# T03-GSM-Schematic.net
KiCad netlist of a schematic drawn in EAGLE
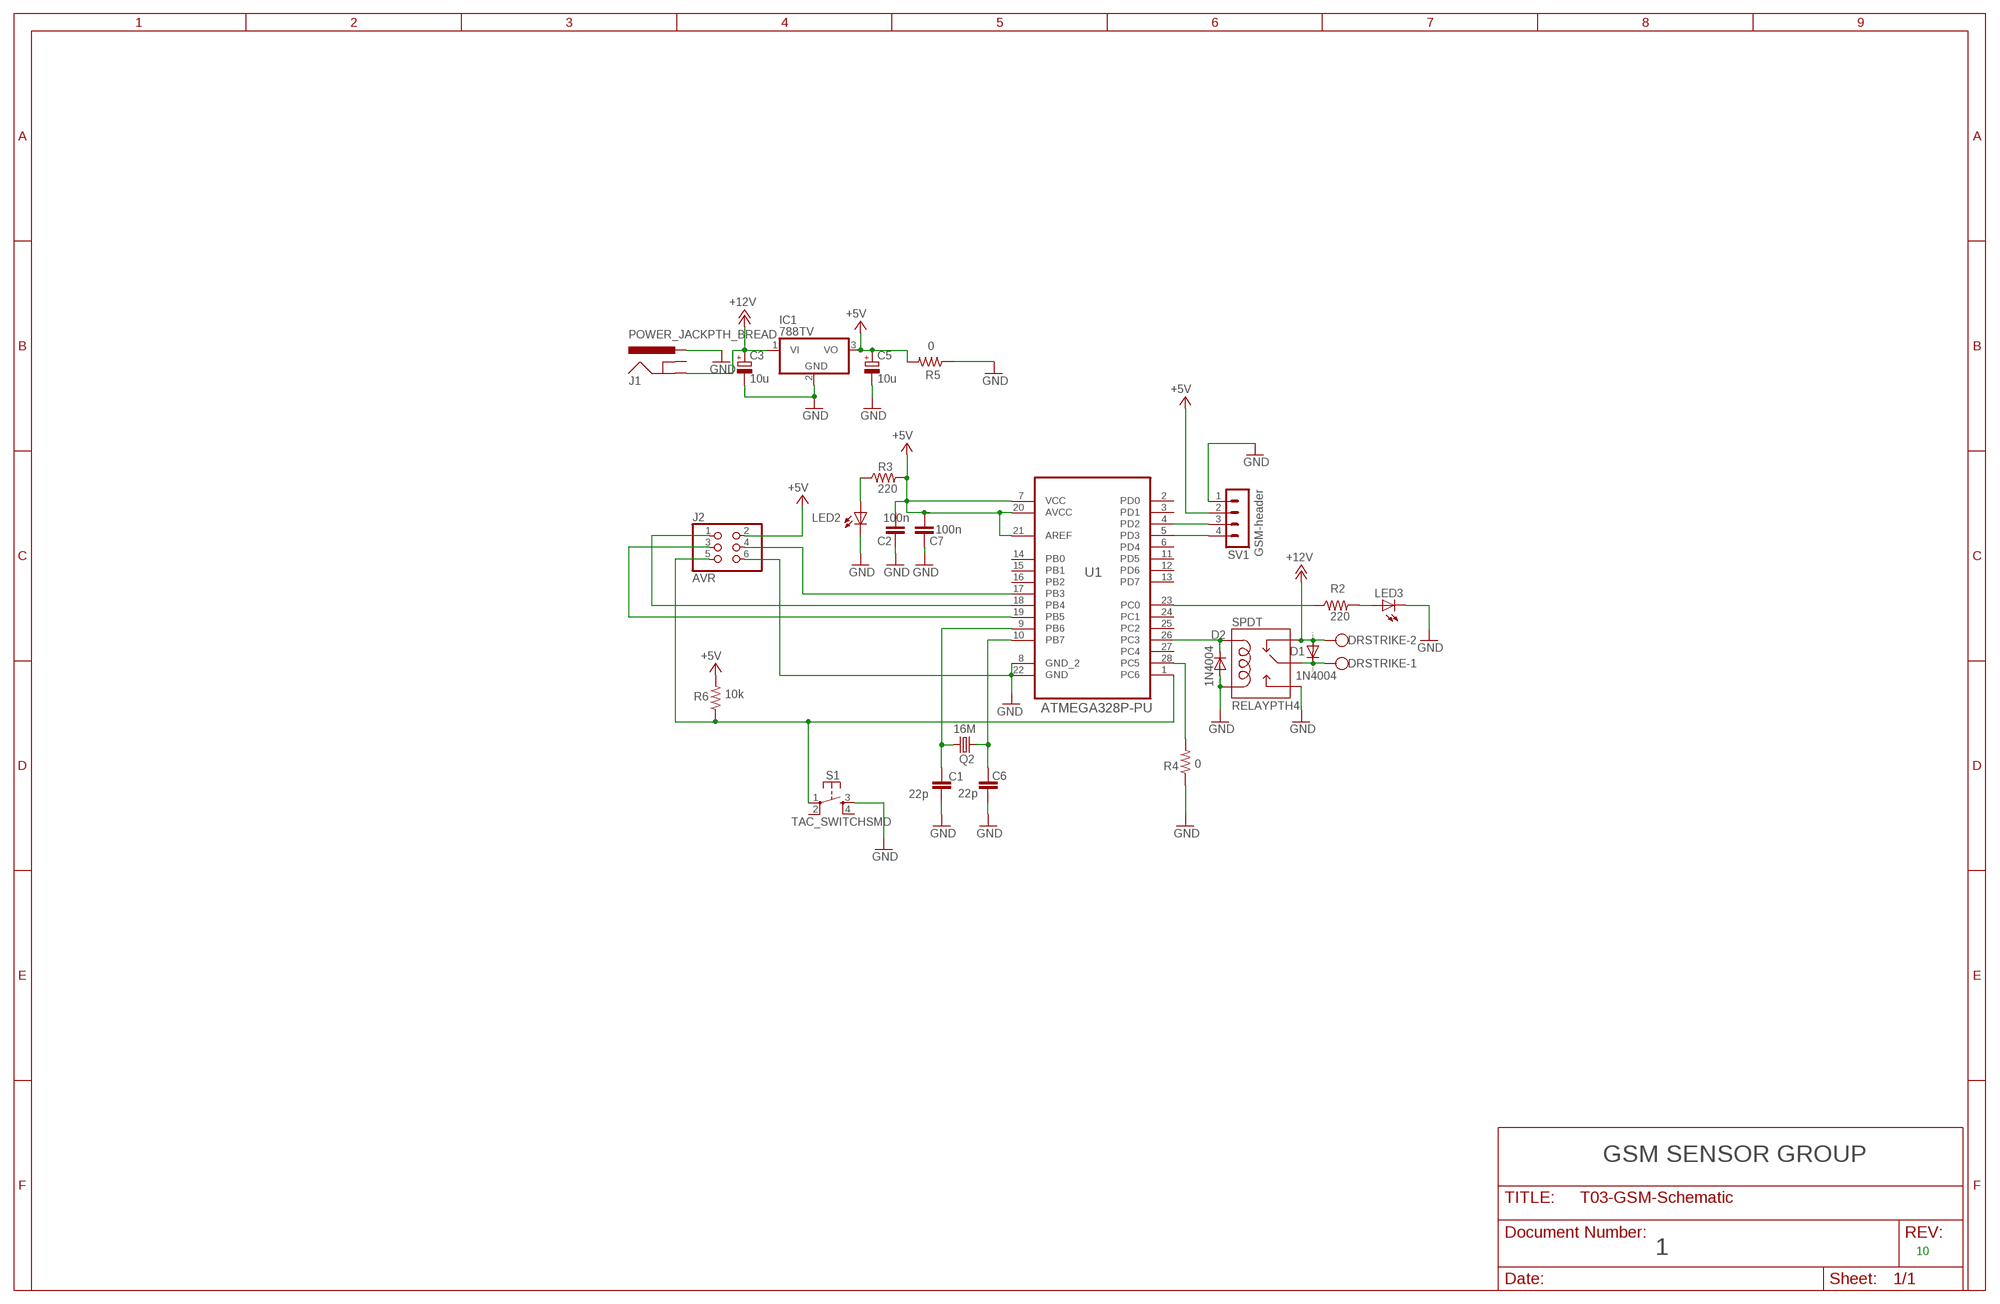
[diagram p0: schematic, sheet 1]

(export (version "E")
  (design (tool "Eeschema 10.0.6"))
  (components
    (comp (ref "C1")
      (value "22p")
      (footprint "eagle-import:C0603")
      (libsource (lib "eagle-import") (part "C-EUC0603"))
    )
    (comp (ref "C2")
      (value "100n")
      (footprint "eagle-import:C0603")
      (libsource (lib "eagle-import") (part "C-EUC0603"))
    )
    (comp (ref "C3")
      (value "10u")
      (footprint "eagle-import:E5-10,5")
      (libsource (lib "eagle-import") (part "CPOL-EUE5-10.5"))
    )
    (comp (ref "C5")
      (value "10u")
      (footprint "eagle-import:E5-10,5")
      (libsource (lib "eagle-import") (part "CPOL-EUE5-10.5"))
    )
    (comp (ref "C6")
      (value "22p")
      (footprint "eagle-import:C0603")
      (libsource (lib "eagle-import") (part "C-EUC0603"))
    )
    (comp (ref "C7")
      (value "100n")
      (footprint "eagle-import:C0603")
      (libsource (lib "eagle-import") (part "C-EUC0603"))
    )
    (comp (ref "D1")
      (value "1N4004")
      (footprint "eagle-import:DO41-10")
      (libsource (lib "eagle-import") (part "1N4004"))
    )
    (comp (ref "D2")
      (value "1N4004")
      (footprint "eagle-import:DO41-10")
      (libsource (lib "eagle-import") (part "1N4004"))
    )
    (comp (ref "DRSTRIKE")
      (value "W237-102")
      (footprint "eagle-import:W237-102")
      (fields (field (name "MPN") "237-102"))
      (libsource (lib "eagle-import") (part "W237-102"))
    )
    (comp (ref "IC1")
      (value "788TV")
      (footprint "eagle-import:TO220V")
      (libsource (lib "eagle-import") (part "78TV8"))
    )
    (comp (ref "J1")
      (value "POWER_JACKPTH_BREAD")
      (footprint "eagle-import:POWER_JACK_PTH_BREAD")
      (libsource (lib "eagle-import") (part "POWER_JACKPTH_BREAD"))
    )
    (comp (ref "J2")
      (value "AVR")
      (footprint "eagle-import:2X03")
      (libsource (lib "eagle-import") (part "PINHD-2X3"))
    )
    (comp (ref "LED2")
      (value "LEDSML0603")
      (footprint "eagle-import:SML0603")
      (libsource (lib "eagle-import") (part "LEDSML0603"))
    )
    (comp (ref "LED3")
      (value "LED5MM")
      (footprint "eagle-import:LED5MM")
      (libsource (lib "eagle-import") (part "LED5MM"))
    )
    (comp (ref "Q2")
      (value "16M")
      (footprint "eagle-import:HC49UP")
      (libsource (lib "eagle-import") (part "CRYSTALHC49UP"))
    )
    (comp (ref "R2")
      (value "220")
      (footprint "eagle-import:R0603")
      (libsource (lib "eagle-import") (part "R-US_R0603"))
    )
    (comp (ref "R3")
      (value "220")
      (footprint "eagle-import:R0603")
      (libsource (lib "eagle-import") (part "R-US_R0603"))
    )
    (comp (ref "R4")
      (value "0")
      (footprint "eagle-import:0204_5")
      (libsource (lib "eagle-import") (part "R-US_0204/5"))
    )
    (comp (ref "R5")
      (value "0")
      (footprint "eagle-import:0204_5")
      (libsource (lib "eagle-import") (part "R-US_0204/5"))
    )
    (comp (ref "R6")
      (value "10k")
      (footprint "eagle-import:R0603")
      (libsource (lib "eagle-import") (part "R-US_R0603"))
    )
    (comp (ref "S1")
      (value "TAC_SWITCHSMD")
      (footprint "eagle-import:TACTILE-SWITCH-SMD")
      (libsource (lib "eagle-import") (part "TAC_SWITCHSMD"))
    )
    (comp (ref "SPDT")
      (value "RELAYPTH4")
      (footprint "eagle-import:RELAY-JZC")
      (libsource (lib "eagle-import") (part "RELAYPTH4"))
    )
    (comp (ref "SV1")
      (value "GSM-header")
      (footprint "eagle-import:MA04-1")
      (libsource (lib "eagle-import") (part "MA04-1"))
    )
    (comp (ref "U1")
      (value "ATMEGA328P-PU")
      (footprint "eagle-import:DIP254P762X457-28")
      (libsource (lib "eagle-import") (part "ATMEGA328P-PU"))
    )
  )
  (nets
    (net (code "1") (name "+5V") (class "Default")
      (node (ref "C2") (pin "2") (pinfunction "2_2") (pintype "passive"))
      (node (ref "C5") (pin "+") (pinfunction "+_+") (pintype "passive"))
      (node (ref "C7") (pin "2") (pinfunction "2_2") (pintype "passive"))
      (node (ref "IC1") (pin "3") (pinfunction "VO_3") (pintype "passive"))
      (node (ref "J2") (pin "2") (pinfunction "2_2") (pintype "passive"))
      (node (ref "R3") (pin "2") (pinfunction "2_2") (pintype "passive"))
      (node (ref "R5") (pin "2") (pinfunction "2_2") (pintype "passive"))
      (node (ref "R6") (pin "2") (pinfunction "2_2") (pintype "passive"))
      (node (ref "SV1") (pin "2") (pinfunction "2_2") (pintype "passive"))
      (node (ref "U1") (pin "20") (pinfunction "AVCC_20") (pintype "power_in"))
      (node (ref "U1") (pin "21") (pinfunction "AREF_21") (pintype "input"))
      (node (ref "U1") (pin "7") (pinfunction "VCC_7") (pintype "power_in"))
    )
    (net (code "2") (name "+12V") (class "Default")
      (node (ref "C3") (pin "+") (pinfunction "+_+") (pintype "passive"))
      (node (ref "D1") (pin "A") (pinfunction "A_A") (pintype "passive"))
      (node (ref "DRSTRIKE") (pin "2") (pinfunction "KL_2") (pintype "passive"))
      (node (ref "IC1") (pin "1") (pinfunction "VI_1") (pintype "input"))
      (node (ref "J1") (pin "GND") (pinfunction "GND_GND") (pintype "bidirectional"))
      (node (ref "SPDT") (pin "2") (pinfunction "NC_2") (pintype "bidirectional"))
    )
    (net (code "3") (name "GND") (class "Default")
      (node (ref "C1") (pin "2") (pinfunction "2_2") (pintype "passive"))
      (node (ref "C2") (pin "1") (pinfunction "1_1") (pintype "passive"))
      (node (ref "C3") (pin "-") (pinfunction "-_-") (pintype "passive"))
      (node (ref "C5") (pin "-") (pinfunction "-_-") (pintype "passive"))
      (node (ref "C6") (pin "2") (pinfunction "2_2") (pintype "passive"))
      (node (ref "C7") (pin "1") (pinfunction "1_1") (pintype "passive"))
      (node (ref "D2") (pin "A") (pinfunction "A_A") (pintype "passive"))
      (node (ref "IC1") (pin "2") (pinfunction "GND_2") (pintype "passive"))
      (node (ref "J1") (pin "PWR") (pinfunction "PWR_PWR") (pintype "bidirectional"))
      (node (ref "J2") (pin "6") (pinfunction "6_6") (pintype "passive"))
      (node (ref "LED2") (pin "C") (pinfunction "C_C") (pintype "passive"))
      (node (ref "LED3") (pin "K") (pinfunction "C_K") (pintype "passive"))
      (node (ref "R4") (pin "1") (pinfunction "1_1") (pintype "passive"))
      (node (ref "R5") (pin "1") (pinfunction "1_1") (pintype "passive"))
      (node (ref "S1") (pin "3") (pinfunction "3_3") (pintype "passive"))
      (node (ref "SPDT") (pin "1") (pinfunction "COIL2_1") (pintype "bidirectional"))
      (node (ref "SPDT") (pin "3") (pinfunction "NO_3") (pintype "bidirectional"))
      (node (ref "SV1") (pin "1") (pinfunction "1_1") (pintype "passive"))
      (node (ref "U1") (pin "22") (pinfunction "GND_22") (pintype "passive"))
      (node (ref "U1") (pin "8") (pinfunction "GND_2_8") (pintype "passive"))
    )
    (net (code "4") (name "Net-(DRSTRIKEA-KL)") (class "Default")
      (node (ref "D1") (pin "C") (pinfunction "C_C") (pintype "passive"))
      (node (ref "DRSTRIKE") (pin "1") (pinfunction "KL_1") (pintype "passive"))
      (node (ref "SPDT") (pin "4") (pinfunction "MAIN_4") (pintype "bidirectional"))
    )
    (net (code "5") (name "Net-(LED2-PadA)") (class "Default")
      (node (ref "LED2") (pin "A") (pinfunction "A_A") (pintype "passive"))
      (node (ref "R3") (pin "1") (pinfunction "1_1") (pintype "passive"))
    )
    (net (code "6") (name "Net-(LED3-PadA)") (class "Default")
      (node (ref "LED3") (pin "A") (pinfunction "A_A") (pintype "passive"))
      (node (ref "R2") (pin "2") (pinfunction "2_2") (pintype "passive"))
    )
    (net (code "7") (name "Net-(SPDT-COIL1)") (class "Default")
      (node (ref "D2") (pin "C") (pinfunction "C_C") (pintype "passive"))
      (node (ref "SPDT") (pin "5") (pinfunction "COIL1_5") (pintype "bidirectional"))
      (node (ref "U1") (pin "26") (pinfunction "PC3_26") (pintype "bidirectional"))
    )
    (net (code "8") (name "Net-(U1-PB3)") (class "Default")
      (node (ref "J2") (pin "4") (pinfunction "4_4") (pintype "passive"))
      (node (ref "U1") (pin "17") (pinfunction "PB3_17") (pintype "bidirectional"))
    )
    (net (code "9") (name "Net-(U1-PB4)") (class "Default")
      (node (ref "J2") (pin "1") (pinfunction "1_1") (pintype "passive"))
      (node (ref "U1") (pin "18") (pinfunction "PB4_18") (pintype "bidirectional"))
    )
    (net (code "10") (name "Net-(U1-PB5)") (class "Default")
      (node (ref "J2") (pin "3") (pinfunction "3_3") (pintype "passive"))
      (node (ref "U1") (pin "19") (pinfunction "PB5_19") (pintype "bidirectional"))
    )
    (net (code "11") (name "Net-(U1-PB6)") (class "Default")
      (node (ref "C1") (pin "1") (pinfunction "1_1") (pintype "passive"))
      (node (ref "Q2") (pin "2") (pinfunction "2_2") (pintype "passive"))
      (node (ref "U1") (pin "9") (pinfunction "PB6_9") (pintype "bidirectional"))
    )
    (net (code "12") (name "Net-(U1-PB7)") (class "Default")
      (node (ref "C6") (pin "1") (pinfunction "1_1") (pintype "passive"))
      (node (ref "Q2") (pin "1") (pinfunction "1_1") (pintype "passive"))
      (node (ref "U1") (pin "10") (pinfunction "PB7_10") (pintype "bidirectional"))
    )
    (net (code "13") (name "Net-(U1-PC0)") (class "Default")
      (node (ref "R2") (pin "1") (pinfunction "1_1") (pintype "passive"))
      (node (ref "U1") (pin "23") (pinfunction "PC0_23") (pintype "bidirectional"))
    )
    (net (code "14") (name "Net-(U1-PC5)") (class "Default")
      (node (ref "R4") (pin "2") (pinfunction "2_2") (pintype "passive"))
      (node (ref "U1") (pin "28") (pinfunction "PC5_28") (pintype "bidirectional"))
    )
    (net (code "15") (name "Net-(U1-PC6)") (class "Default")
      (node (ref "J2") (pin "5") (pinfunction "5_5") (pintype "passive"))
      (node (ref "R6") (pin "1") (pinfunction "1_1") (pintype "passive"))
      (node (ref "S1") (pin "1") (pinfunction "1_1") (pintype "passive"))
      (node (ref "U1") (pin "1") (pinfunction "PC6_1") (pintype "bidirectional"))
    )
    (net (code "16") (name "Net-(U1-PD2)") (class "Default")
      (node (ref "SV1") (pin "3") (pinfunction "3_3") (pintype "passive"))
      (node (ref "U1") (pin "4") (pinfunction "PD2_4") (pintype "bidirectional"))
    )
    (net (code "17") (name "Net-(U1-PD3)") (class "Default")
      (node (ref "SV1") (pin "4") (pinfunction "4_4") (pintype "passive"))
      (node (ref "U1") (pin "5") (pinfunction "PD3_5") (pintype "bidirectional"))
    )
    (net (code "18") (name "unconnected-(J1-PadGNDBREAK)") (class "Default")
      (node (ref "J1") (pin "GNDBREAK") (pinfunction "GNDBREAK_GNDBREAK") (pintype "bidirectional"))
    )
    (net (code "19") (name "unconnected-(S1-Pad2)") (class "Default")
      (node (ref "S1") (pin "2") (pinfunction "2_2") (pintype "passive"))
    )
    (net (code "20") (name "unconnected-(S1-Pad4)") (class "Default")
      (node (ref "S1") (pin "4") (pinfunction "4_4") (pintype "passive"))
    )
    (net (code "21") (name "unconnected-(U1-PB0-Pad14)") (class "Default")
      (node (ref "U1") (pin "14") (pinfunction "PB0_14") (pintype "bidirectional"))
    )
    (net (code "22") (name "unconnected-(U1-PB1-Pad15)") (class "Default")
      (node (ref "U1") (pin "15") (pinfunction "PB1_15") (pintype "bidirectional"))
    )
    (net (code "23") (name "unconnected-(U1-PB2-Pad16)") (class "Default")
      (node (ref "U1") (pin "16") (pinfunction "PB2_16") (pintype "bidirectional"))
    )
    (net (code "24") (name "unconnected-(U1-PC1-Pad24)") (class "Default")
      (node (ref "U1") (pin "24") (pinfunction "PC1_24") (pintype "bidirectional"))
    )
    (net (code "25") (name "unconnected-(U1-PC2-Pad25)") (class "Default")
      (node (ref "U1") (pin "25") (pinfunction "PC2_25") (pintype "bidirectional"))
    )
    (net (code "26") (name "unconnected-(U1-PC4-Pad27)") (class "Default")
      (node (ref "U1") (pin "27") (pinfunction "PC4_27") (pintype "bidirectional"))
    )
    (net (code "27") (name "unconnected-(U1-PD0-Pad2)") (class "Default")
      (node (ref "U1") (pin "2") (pinfunction "PD0_2") (pintype "bidirectional"))
    )
    (net (code "28") (name "unconnected-(U1-PD1-Pad3)") (class "Default")
      (node (ref "U1") (pin "3") (pinfunction "PD1_3") (pintype "bidirectional"))
    )
    (net (code "29") (name "unconnected-(U1-PD4-Pad6)") (class "Default")
      (node (ref "U1") (pin "6") (pinfunction "PD4_6") (pintype "bidirectional"))
    )
    (net (code "30") (name "unconnected-(U1-PD5-Pad11)") (class "Default")
      (node (ref "U1") (pin "11") (pinfunction "PD5_11") (pintype "bidirectional"))
    )
    (net (code "31") (name "unconnected-(U1-PD6-Pad12)") (class "Default")
      (node (ref "U1") (pin "12") (pinfunction "PD6_12") (pintype "bidirectional"))
    )
    (net (code "32") (name "unconnected-(U1-PD7-Pad13)") (class "Default")
      (node (ref "U1") (pin "13") (pinfunction "PD7_13") (pintype "bidirectional"))
    )
  )
)
